# M710.net
KiCad netlist of a schematic drawn in EAGLE
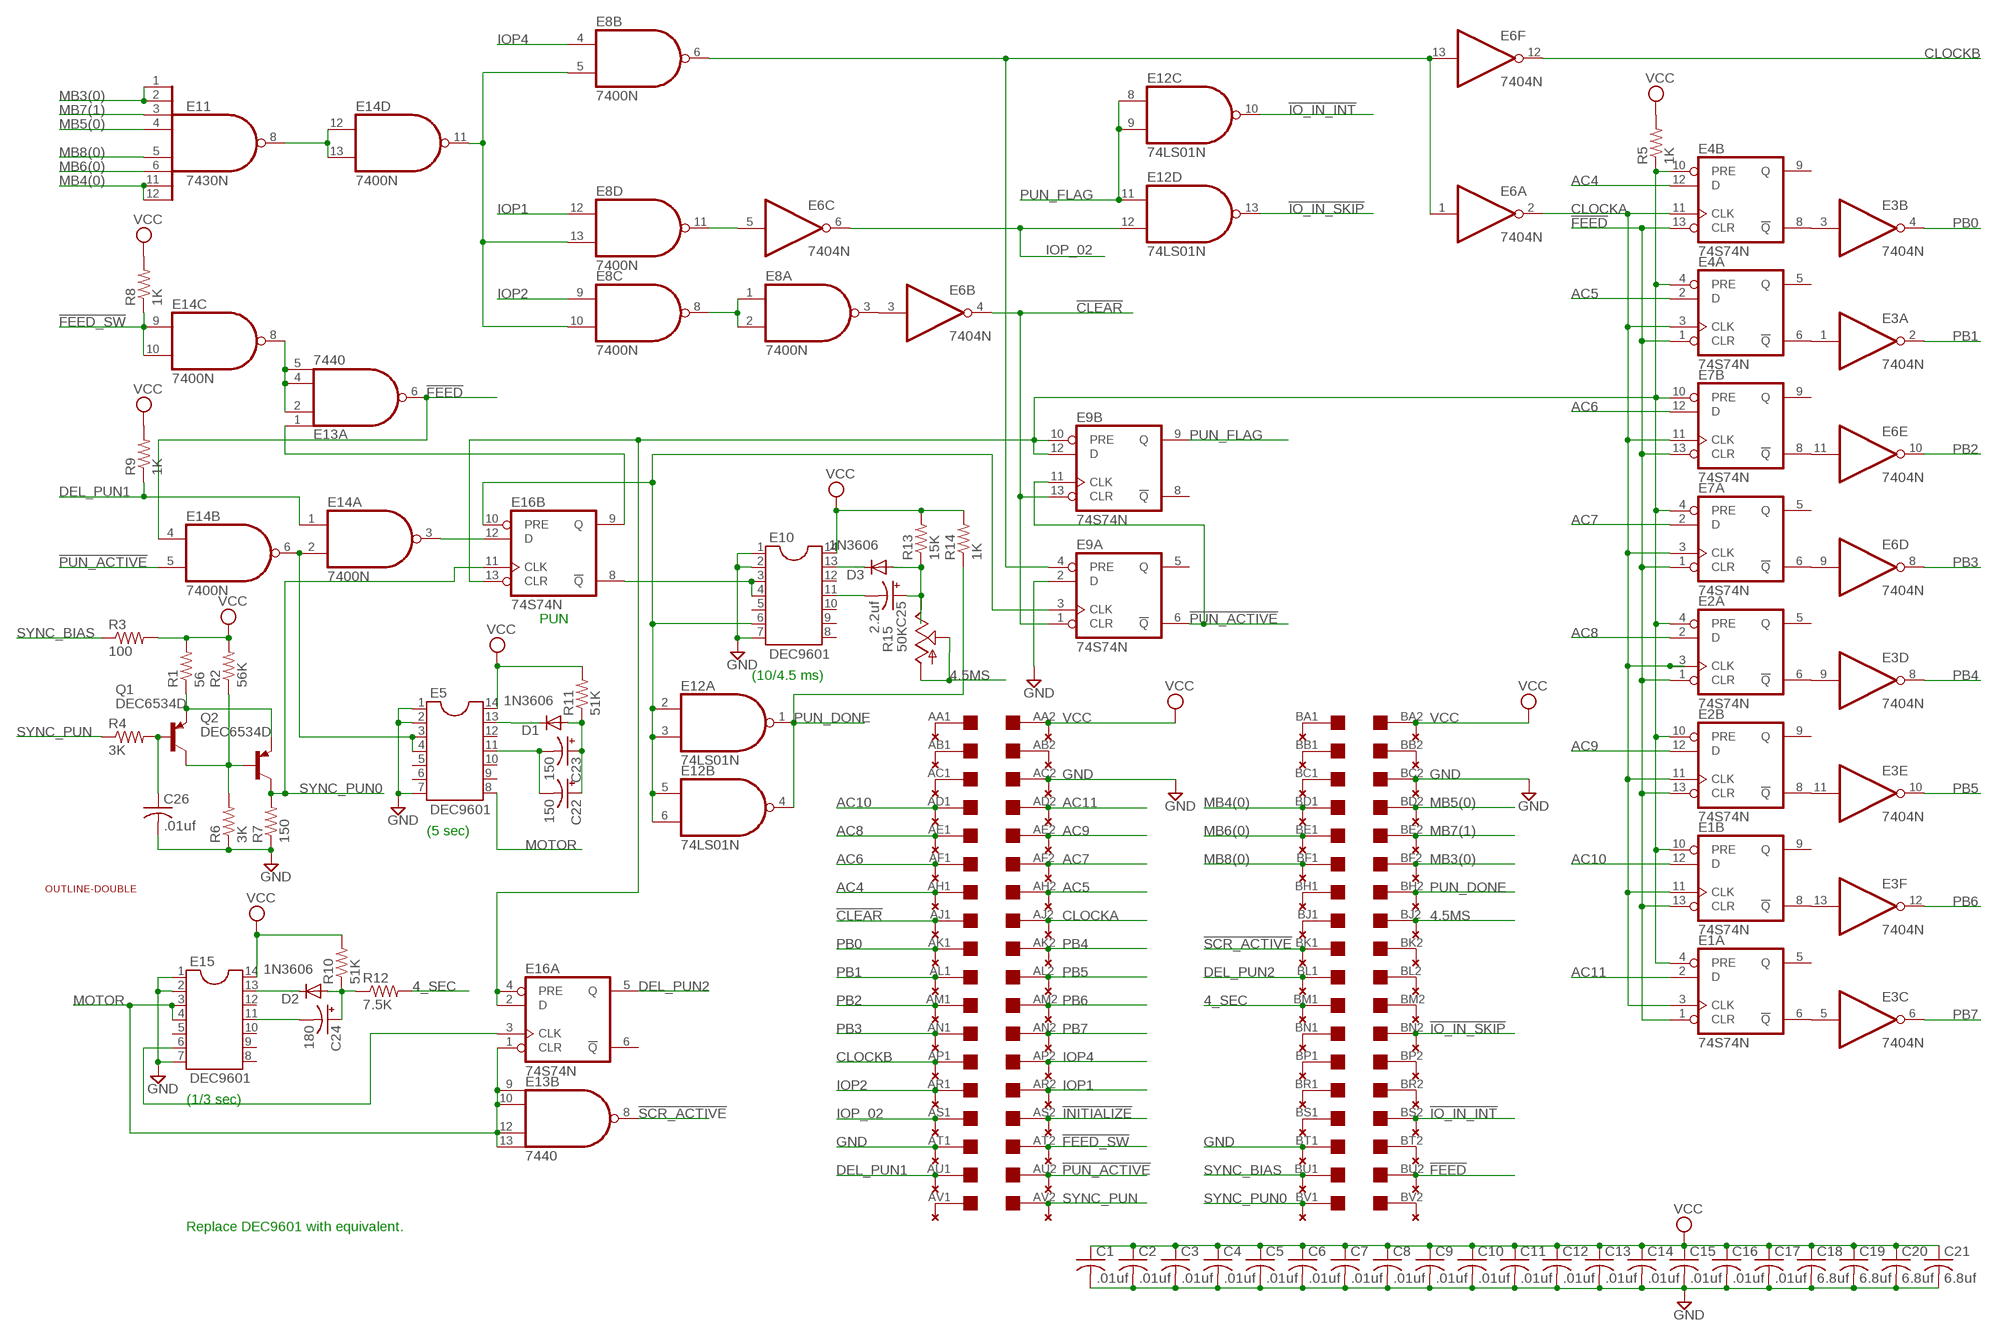
[diagram p0: schematic, sheet 1]

(export (version "E")
  (design (tool "Eeschema 10.0.6"))
  (components
    (comp (ref "C1")
      (value ".01uf")
      (footprint "eagle-import:C050-025X075")
      (libsource (lib "eagle-import") (part "C-US050-025X075"))
    )
    (comp (ref "C2")
      (value ".01uf")
      (footprint "eagle-import:C050-025X075")
      (libsource (lib "eagle-import") (part "C-US050-025X075"))
    )
    (comp (ref "C3")
      (value ".01uf")
      (footprint "eagle-import:C050-025X075")
      (libsource (lib "eagle-import") (part "C-US050-025X075"))
    )
    (comp (ref "C4")
      (value ".01uf")
      (footprint "eagle-import:C050-025X075")
      (libsource (lib "eagle-import") (part "C-US050-025X075"))
    )
    (comp (ref "C5")
      (value ".01uf")
      (footprint "eagle-import:C050-025X075")
      (libsource (lib "eagle-import") (part "C-US050-025X075"))
    )
    (comp (ref "C6")
      (value ".01uf")
      (footprint "eagle-import:C050-025X075")
      (libsource (lib "eagle-import") (part "C-US050-025X075"))
    )
    (comp (ref "C7")
      (value ".01uf")
      (footprint "eagle-import:C050-025X075")
      (libsource (lib "eagle-import") (part "C-US050-025X075"))
    )
    (comp (ref "C8")
      (value ".01uf")
      (footprint "eagle-import:C050-025X075")
      (libsource (lib "eagle-import") (part "C-US050-025X075"))
    )
    (comp (ref "C9")
      (value ".01uf")
      (footprint "eagle-import:C050-025X075")
      (libsource (lib "eagle-import") (part "C-US050-025X075"))
    )
    (comp (ref "C10")
      (value ".01uf")
      (footprint "eagle-import:C050-025X075")
      (libsource (lib "eagle-import") (part "C-US050-025X075"))
    )
    (comp (ref "C11")
      (value ".01uf")
      (footprint "eagle-import:C050-025X075")
      (libsource (lib "eagle-import") (part "C-US050-025X075"))
    )
    (comp (ref "C12")
      (value ".01uf")
      (footprint "eagle-import:C050-025X075")
      (libsource (lib "eagle-import") (part "C-US050-025X075"))
    )
    (comp (ref "C13")
      (value ".01uf")
      (footprint "eagle-import:C050-025X075")
      (libsource (lib "eagle-import") (part "C-US050-025X075"))
    )
    (comp (ref "C14")
      (value ".01uf")
      (footprint "eagle-import:C050-025X075")
      (libsource (lib "eagle-import") (part "C-US050-025X075"))
    )
    (comp (ref "C15")
      (value ".01uf")
      (footprint "eagle-import:C050-025X075")
      (libsource (lib "eagle-import") (part "C-US050-025X075"))
    )
    (comp (ref "C16")
      (value ".01uf")
      (footprint "eagle-import:C050-025X075")
      (libsource (lib "eagle-import") (part "C-US050-025X075"))
    )
    (comp (ref "C17")
      (value ".01uf")
      (footprint "eagle-import:C050-025X075")
      (libsource (lib "eagle-import") (part "C-US050-025X075"))
    )
    (comp (ref "C18")
      (value "6.8uf")
      (footprint "eagle-import:C150-054X183")
      (libsource (lib "eagle-import") (part "C-US150-054X183"))
    )
    (comp (ref "C19")
      (value "6.8uf")
      (footprint "eagle-import:C150-054X183")
      (libsource (lib "eagle-import") (part "C-US150-054X183"))
    )
    (comp (ref "C20")
      (value "6.8uf")
      (footprint "eagle-import:C150-054X183")
      (libsource (lib "eagle-import") (part "C-US150-054X183"))
    )
    (comp (ref "C21")
      (value "6.8uf")
      (footprint "eagle-import:C150-054X183")
      (libsource (lib "eagle-import") (part "C-US150-054X183"))
    )
    (comp (ref "C22")
      (value "150")
      (footprint "eagle-import:E5-8,5")
      (libsource (lib "eagle-import") (part "CPOL-USE5-8.5"))
    )
    (comp (ref "C23")
      (value "150")
      (footprint "eagle-import:E5-8,5")
      (libsource (lib "eagle-import") (part "CPOL-USE5-8.5"))
    )
    (comp (ref "C24")
      (value "180")
      (footprint "eagle-import:E5-8,5")
      (libsource (lib "eagle-import") (part "CPOL-USE5-8.5"))
    )
    (comp (ref "C25")
      (value "2.2uf")
      (footprint "eagle-import:E5-8,5")
      (libsource (lib "eagle-import") (part "CPOL-USE5-8.5"))
    )
    (comp (ref "C26")
      (value ".01uf")
      (footprint "eagle-import:C050-025X075")
      (libsource (lib "eagle-import") (part "C-US050-025X075"))
    )
    (comp (ref "D1")
      (value "1N3606")
      (footprint "eagle-import:DO41-10")
      (libsource (lib "eagle-import") (part "1N4004"))
    )
    (comp (ref "D2")
      (value "1N3606")
      (footprint "eagle-import:DO41-10")
      (libsource (lib "eagle-import") (part "1N4004"))
    )
    (comp (ref "D3")
      (value "1N3606")
      (footprint "eagle-import:DO41-10")
      (libsource (lib "eagle-import") (part "1N4004"))
    )
    (comp (ref "E1")
      (value "74S74N")
      (footprint "eagle-import:DIL14")
      (libsource (lib "eagle-import") (part "7474NS"))
    )
    (comp (ref "E2")
      (value "74S74N")
      (footprint "eagle-import:DIL14")
      (libsource (lib "eagle-import") (part "7474NS"))
    )
    (comp (ref "E3")
      (value "7404N")
      (footprint "eagle-import:DIL14")
      (libsource (lib "eagle-import") (part "7404N"))
    )
    (comp (ref "E4")
      (value "74S74N")
      (footprint "eagle-import:DIL14")
      (libsource (lib "eagle-import") (part "7474NS"))
    )
    (comp (ref "E5")
      (value "DEC9601")
      (footprint "eagle-import:DIL14")
      (libsource (lib "eagle-import") (part "DIL14"))
    )
    (comp (ref "E6")
      (value "7404N")
      (footprint "eagle-import:DIL14")
      (libsource (lib "eagle-import") (part "7404N"))
    )
    (comp (ref "E7")
      (value "74S74N")
      (footprint "eagle-import:DIL14")
      (libsource (lib "eagle-import") (part "7474NS"))
    )
    (comp (ref "E8")
      (value "7400N")
      (footprint "eagle-import:DIL14")
      (libsource (lib "eagle-import") (part "7400N"))
    )
    (comp (ref "E9")
      (value "74S74N")
      (footprint "eagle-import:DIL14")
      (libsource (lib "eagle-import") (part "7474NS"))
    )
    (comp (ref "E10")
      (value "DEC9601")
      (footprint "eagle-import:DIL14")
      (libsource (lib "eagle-import") (part "DIL14"))
    )
    (comp (ref "E11")
      (value "7430N")
      (footprint "eagle-import:DIL14")
      (libsource (lib "eagle-import") (part "7430N"))
    )
    (comp (ref "E12")
      (value "74LS01N")
      (footprint "eagle-import:DIL14")
      (libsource (lib "eagle-import") (part "7401NLS"))
    )
    (comp (ref "E13")
      (value "7440")
      (footprint "eagle-import:DIL14")
      (libsource (lib "eagle-import") (part "7420NS"))
    )
    (comp (ref "E14")
      (value "7400N")
      (footprint "eagle-import:DIL14")
      (libsource (lib "eagle-import") (part "7400N"))
    )
    (comp (ref "E15")
      (value "DEC9601")
      (footprint "eagle-import:DIL14")
      (libsource (lib "eagle-import") (part "DIL14"))
    )
    (comp (ref "E16")
      (value "74S74N")
      (footprint "eagle-import:DIL14")
      (libsource (lib "eagle-import") (part "7474NS"))
    )
    (comp (ref "Q1")
      (value "DEC6534D")
      (footprint "eagle-import:TO92")
      (libsource (lib "eagle-import") (part "2N3906"))
    )
    (comp (ref "Q2")
      (value "DEC6534D")
      (footprint "eagle-import:TO92")
      (libsource (lib "eagle-import") (part "2N3906"))
    )
    (comp (ref "R1")
      (value "56")
      (footprint "eagle-import:0207_7")
      (libsource (lib "eagle-import") (part "R-US_0207/7"))
    )
    (comp (ref "R2")
      (value "56K")
      (footprint "eagle-import:0207_7")
      (libsource (lib "eagle-import") (part "R-US_0207/7"))
    )
    (comp (ref "R3")
      (value "100")
      (footprint "eagle-import:0207_7")
      (libsource (lib "eagle-import") (part "R-US_0207/7"))
    )
    (comp (ref "R4")
      (value "3K")
      (footprint "eagle-import:0207_7")
      (libsource (lib "eagle-import") (part "R-US_0207/7"))
    )
    (comp (ref "R5")
      (value "1K")
      (footprint "eagle-import:0207_7")
      (libsource (lib "eagle-import") (part "R-US_0207/7"))
    )
    (comp (ref "R6")
      (value "3K")
      (footprint "eagle-import:0207_7")
      (libsource (lib "eagle-import") (part "R-US_0207/7"))
    )
    (comp (ref "R7")
      (value "150")
      (footprint "eagle-import:0207_7")
      (libsource (lib "eagle-import") (part "R-US_0207/7"))
    )
    (comp (ref "R8")
      (value "1K")
      (footprint "eagle-import:0207_7")
      (libsource (lib "eagle-import") (part "R-US_0207/7"))
    )
    (comp (ref "R9")
      (value "1K")
      (footprint "eagle-import:0207_7")
      (libsource (lib "eagle-import") (part "R-US_0207/7"))
    )
    (comp (ref "R10")
      (value "51K")
      (footprint "eagle-import:0207_7")
      (libsource (lib "eagle-import") (part "R-US_0207/7"))
    )
    (comp (ref "R11")
      (value "51K")
      (footprint "eagle-import:0207_7")
      (libsource (lib "eagle-import") (part "R-US_0207/7"))
    )
    (comp (ref "R12")
      (value "7.5K")
      (footprint "eagle-import:0207_7")
      (libsource (lib "eagle-import") (part "R-US_0207/7"))
    )
    (comp (ref "R13")
      (value "15K")
      (footprint "eagle-import:0207_7")
      (libsource (lib "eagle-import") (part "R-US_0207/7"))
    )
    (comp (ref "R14")
      (value "1K")
      (footprint "eagle-import:0207_7")
      (libsource (lib "eagle-import") (part "R-US_0207/7"))
    )
    (comp (ref "R15")
      (value "50K")
      (footprint "eagle-import:PT-SPIN")
      (libsource (lib "eagle-import") (part "TRIM_US-PTSPIN"))
    )
    (comp (ref "U$1")
      (value "OUTLINE-DOUBLE")
      (footprint "eagle-import:DOUBLE")
      (libsource (lib "eagle-import") (part "OUTLINE-DOUBLE"))
    )
    (comp (ref "U$2")
      (value "DOUBLE")
      (footprint "eagle-import:EDGE-CON4")
      (libsource (lib "eagle-import") (part "DOUBLE"))
    )
    (comp (ref "U$5")
      (value "THRU-HOLE2")
      (footprint "eagle-import:THRU-HOLEB")
      (libsource (lib "eagle-import") (part "THRU-HOLE2"))
    )
    (comp (ref "U$7")
      (value "THRU-HOLE2")
      (footprint "eagle-import:THRU-HOLEB")
      (libsource (lib "eagle-import") (part "THRU-HOLE2"))
    )
  )
  (nets
    (net (code "1") (name "/4.5MS") (class "Default")
      (node (ref "R15") (pin "A") (pinfunction "A_A") (pintype "passive"))
      (node (ref "R15") (pin "S") (pinfunction "S_S") (pintype "passive"))
      (node (ref "U$2") (pin "BJ2") (pinfunction "1_BJ2") (pintype "bidirectional"))
      (node (ref "U$5") (pin "J2") (pinfunction "P$1_J2") (pintype "passive"))
    )
    (net (code "2") (name "/4_SEC") (class "Default")
      (node (ref "R12") (pin "2") (pinfunction "2_2") (pintype "passive"))
      (node (ref "U$2") (pin "BM1") (pinfunction "1_BM1") (pintype "bidirectional"))
      (node (ref "U$5") (pin "M1") (pinfunction "P$1_M1") (pintype "passive"))
    )
    (net (code "3") (name "/AC4") (class "Default")
      (node (ref "E4") (pin "12") (pinfunction "D_12") (pintype "input"))
      (node (ref "U$2") (pin "AH1") (pinfunction "1_AH1") (pintype "bidirectional"))
      (node (ref "U$7") (pin "H1") (pinfunction "P$1_H1") (pintype "passive"))
    )
    (net (code "4") (name "/AC5") (class "Default")
      (node (ref "E4") (pin "2") (pinfunction "D_2") (pintype "input"))
      (node (ref "U$2") (pin "AH2") (pinfunction "1_AH2") (pintype "bidirectional"))
      (node (ref "U$7") (pin "H2") (pinfunction "P$1_H2") (pintype "passive"))
    )
    (net (code "5") (name "/AC6") (class "Default")
      (node (ref "E7") (pin "12") (pinfunction "D_12") (pintype "input"))
      (node (ref "U$2") (pin "AF1") (pinfunction "1_AF1") (pintype "bidirectional"))
      (node (ref "U$7") (pin "F1") (pinfunction "P$1_F1") (pintype "passive"))
    )
    (net (code "6") (name "/AC7") (class "Default")
      (node (ref "E7") (pin "2") (pinfunction "D_2") (pintype "input"))
      (node (ref "U$2") (pin "AF2") (pinfunction "1_AF2") (pintype "bidirectional"))
      (node (ref "U$7") (pin "F2") (pinfunction "P$1_F2") (pintype "passive"))
    )
    (net (code "7") (name "/AC8") (class "Default")
      (node (ref "E2") (pin "2") (pinfunction "D_2") (pintype "input"))
      (node (ref "U$2") (pin "AE1") (pinfunction "1_AE1") (pintype "bidirectional"))
      (node (ref "U$7") (pin "E1") (pinfunction "P$1_E1") (pintype "passive"))
    )
    (net (code "8") (name "/AC9") (class "Default")
      (node (ref "E2") (pin "12") (pinfunction "D_12") (pintype "input"))
      (node (ref "U$2") (pin "AE2") (pinfunction "1_AE2") (pintype "bidirectional"))
      (node (ref "U$7") (pin "E2") (pinfunction "P$1_E2") (pintype "passive"))
    )
    (net (code "9") (name "/AC10") (class "Default")
      (node (ref "E1") (pin "12") (pinfunction "D_12") (pintype "input"))
      (node (ref "U$2") (pin "AD1") (pinfunction "1_AD1") (pintype "bidirectional"))
      (node (ref "U$7") (pin "D1") (pinfunction "P$1_D1") (pintype "passive"))
    )
    (net (code "10") (name "/AC11") (class "Default")
      (node (ref "E1") (pin "2") (pinfunction "D_2") (pintype "input"))
      (node (ref "U$2") (pin "AD2") (pinfunction "1_AD2") (pintype "bidirectional"))
      (node (ref "U$7") (pin "D2") (pinfunction "P$1_D2") (pintype "passive"))
    )
    (net (code "11") (name "/CLOCKA") (class "Default")
      (node (ref "E1") (pin "11") (pinfunction "CLK_11") (pintype "input"))
      (node (ref "E1") (pin "3") (pinfunction "CLK_3") (pintype "input"))
      (node (ref "E2") (pin "11") (pinfunction "CLK_11") (pintype "input"))
      (node (ref "E2") (pin "3") (pinfunction "CLK_3") (pintype "input"))
      (node (ref "E4") (pin "11") (pinfunction "CLK_11") (pintype "input"))
      (node (ref "E4") (pin "3") (pinfunction "CLK_3") (pintype "input"))
      (node (ref "E6") (pin "2") (pinfunction "O_2") (pintype "output"))
      (node (ref "E7") (pin "11") (pinfunction "CLK_11") (pintype "input"))
      (node (ref "E7") (pin "3") (pinfunction "CLK_3") (pintype "input"))
      (node (ref "U$2") (pin "AJ2") (pinfunction "1_AJ2") (pintype "bidirectional"))
      (node (ref "U$7") (pin "J2") (pinfunction "P$1_J2") (pintype "passive"))
    )
    (net (code "12") (name "/CLOCKB") (class "Default")
      (node (ref "E6") (pin "12") (pinfunction "O_12") (pintype "output"))
      (node (ref "U$2") (pin "AP1") (pinfunction "1_AP1") (pintype "bidirectional"))
      (node (ref "U$7") (pin "P1") (pinfunction "P$1_P1") (pintype "passive"))
    )
    (net (code "13") (name "/DEL_PUN1") (class "Default")
      (node (ref "E14") (pin "1") (pinfunction "I0_1") (pintype "input"))
      (node (ref "R9") (pin "1") (pinfunction "1_1") (pintype "passive"))
      (node (ref "U$2") (pin "AU1") (pinfunction "1_AU1") (pintype "bidirectional"))
      (node (ref "U$7") (pin "U1") (pinfunction "P$1_U1") (pintype "passive"))
    )
    (net (code "14") (name "/DEL_PUN2") (class "Default")
      (node (ref "E16") (pin "5") (pinfunction "Q_5") (pintype "output"))
      (node (ref "U$2") (pin "BL1") (pinfunction "1_BL1") (pintype "bidirectional"))
      (node (ref "U$5") (pin "L1") (pinfunction "P$1_L1") (pintype "passive"))
    )
    (net (code "15") (name "/IOP1") (class "Default")
      (node (ref "E8") (pin "12") (pinfunction "I0_12") (pintype "input"))
      (node (ref "U$2") (pin "AR2") (pinfunction "1_AR2") (pintype "bidirectional"))
      (node (ref "U$7") (pin "R2") (pinfunction "P$1_R2") (pintype "passive"))
    )
    (net (code "16") (name "/IOP2") (class "Default")
      (node (ref "E8") (pin "9") (pinfunction "I0_9") (pintype "input"))
      (node (ref "U$2") (pin "AR1") (pinfunction "1_AR1") (pintype "bidirectional"))
      (node (ref "U$7") (pin "R1") (pinfunction "P$1_R1") (pintype "passive"))
    )
    (net (code "17") (name "/IOP4") (class "Default")
      (node (ref "E8") (pin "4") (pinfunction "I0_4") (pintype "input"))
      (node (ref "U$2") (pin "AP2") (pinfunction "1_AP2") (pintype "bidirectional"))
      (node (ref "U$7") (pin "P2") (pinfunction "P$1_P2") (pintype "passive"))
    )
    (net (code "18") (name "/IOP_02") (class "Default")
      (node (ref "E12") (pin "12") (pinfunction "I1_12") (pintype "input"))
      (node (ref "E6") (pin "6") (pinfunction "O_6") (pintype "output"))
      (node (ref "U$2") (pin "AS1") (pinfunction "1_AS1") (pintype "bidirectional"))
      (node (ref "U$7") (pin "S1") (pinfunction "P$1_S1") (pintype "passive"))
    )
    (net (code "19") (name "/MB3(0)") (class "Default")
      (node (ref "E11") (pin "1") (pinfunction "I0_1") (pintype "input"))
      (node (ref "E11") (pin "2") (pinfunction "I1_2") (pintype "input"))
      (node (ref "U$2") (pin "BF2") (pinfunction "1_BF2") (pintype "bidirectional"))
      (node (ref "U$5") (pin "F2") (pinfunction "P$1_F2") (pintype "passive"))
    )
    (net (code "20") (name "/MB4(0)") (class "Default")
      (node (ref "E11") (pin "11") (pinfunction "I6_11") (pintype "input"))
      (node (ref "E11") (pin "12") (pinfunction "I7_12") (pintype "input"))
      (node (ref "U$2") (pin "BD1") (pinfunction "1_BD1") (pintype "bidirectional"))
      (node (ref "U$5") (pin "D1") (pinfunction "P$1_D1") (pintype "passive"))
    )
    (net (code "21") (name "/MB5(0)") (class "Default")
      (node (ref "E11") (pin "4") (pinfunction "I3_4") (pintype "input"))
      (node (ref "U$2") (pin "BD2") (pinfunction "1_BD2") (pintype "bidirectional"))
      (node (ref "U$5") (pin "D2") (pinfunction "P$1_D2") (pintype "passive"))
    )
    (net (code "22") (name "/MB6(0)") (class "Default")
      (node (ref "E11") (pin "6") (pinfunction "I5_6") (pintype "input"))
      (node (ref "U$2") (pin "BE1") (pinfunction "1_BE1") (pintype "bidirectional"))
      (node (ref "U$5") (pin "E1") (pinfunction "P$1_E1") (pintype "passive"))
    )
    (net (code "23") (name "/MB7(1)") (class "Default")
      (node (ref "E11") (pin "3") (pinfunction "I2_3") (pintype "input"))
      (node (ref "U$2") (pin "BE2") (pinfunction "1_BE2") (pintype "bidirectional"))
      (node (ref "U$5") (pin "E2") (pinfunction "P$1_E2") (pintype "passive"))
    )
    (net (code "24") (name "/MB8(0)") (class "Default")
      (node (ref "E11") (pin "5") (pinfunction "I4_5") (pintype "input"))
      (node (ref "U$2") (pin "BF1") (pinfunction "1_BF1") (pintype "bidirectional"))
      (node (ref "U$5") (pin "F1") (pinfunction "P$1_F1") (pintype "passive"))
    )
    (net (code "25") (name "/MOTOR") (class "Default")
      (node (ref "E13") (pin "10") (pinfunction "I1_10") (pintype "input"))
      (node (ref "E13") (pin "12") (pinfunction "I2_12") (pintype "input"))
      (node (ref "E13") (pin "13") (pinfunction "I3_13") (pintype "input"))
      (node (ref "E13") (pin "9") (pinfunction "I0_9") (pintype "input"))
      (node (ref "E15") (pin "3") (pinfunction "3_3") (pintype "passive"))
      (node (ref "E15") (pin "4") (pinfunction "4_4") (pintype "passive"))
      (node (ref "E16") (pin "1") (pinfunction "CLR_1") (pintype "input"))
      (node (ref "E5") (pin "8") (pinfunction "8_8") (pintype "passive"))
    )
    (net (code "26") (name "/PB0") (class "Default")
      (node (ref "E3") (pin "4") (pinfunction "O_4") (pintype "output"))
      (node (ref "U$2") (pin "AK1") (pinfunction "1_AK1") (pintype "bidirectional"))
      (node (ref "U$7") (pin "K1") (pinfunction "P$1_K1") (pintype "passive"))
    )
    (net (code "27") (name "/PB1") (class "Default")
      (node (ref "E3") (pin "2") (pinfunction "O_2") (pintype "output"))
      (node (ref "U$2") (pin "AL1") (pinfunction "1_AL1") (pintype "bidirectional"))
      (node (ref "U$7") (pin "L1") (pinfunction "P$1_L1") (pintype "passive"))
    )
    (net (code "28") (name "/PB2") (class "Default")
      (node (ref "E6") (pin "10") (pinfunction "O_10") (pintype "output"))
      (node (ref "U$2") (pin "AM1") (pinfunction "1_AM1") (pintype "bidirectional"))
      (node (ref "U$7") (pin "M1") (pinfunction "P$1_M1") (pintype "passive"))
    )
    (net (code "29") (name "/PB3") (class "Default")
      (node (ref "E6") (pin "8") (pinfunction "O_8") (pintype "output"))
      (node (ref "U$2") (pin "AN1") (pinfunction "1_AN1") (pintype "bidirectional"))
      (node (ref "U$7") (pin "N1") (pinfunction "P$1_N1") (pintype "passive"))
    )
    (net (code "30") (name "/PB4") (class "Default")
      (node (ref "E3") (pin "8") (pinfunction "O_8") (pintype "output"))
      (node (ref "U$2") (pin "AK2") (pinfunction "1_AK2") (pintype "bidirectional"))
      (node (ref "U$7") (pin "K2") (pinfunction "P$1_K2") (pintype "passive"))
    )
    (net (code "31") (name "/PB5") (class "Default")
      (node (ref "E3") (pin "10") (pinfunction "O_10") (pintype "output"))
      (node (ref "U$2") (pin "AL2") (pinfunction "1_AL2") (pintype "bidirectional"))
      (node (ref "U$7") (pin "L2") (pinfunction "P$1_L2") (pintype "passive"))
    )
    (net (code "32") (name "/PB6") (class "Default")
      (node (ref "E3") (pin "12") (pinfunction "O_12") (pintype "output"))
      (node (ref "U$2") (pin "AM2") (pinfunction "1_AM2") (pintype "bidirectional"))
      (node (ref "U$7") (pin "M2") (pinfunction "P$1_M2") (pintype "passive"))
    )
    (net (code "33") (name "/PB7") (class "Default")
      (node (ref "E3") (pin "6") (pinfunction "O_6") (pintype "output"))
      (node (ref "U$2") (pin "AN2") (pinfunction "1_AN2") (pintype "bidirectional"))
      (node (ref "U$7") (pin "N2") (pinfunction "P$1_N2") (pintype "passive"))
    )
    (net (code "34") (name "/PUN_DONE") (class "Default")
      (node (ref "E12") (pin "1") (pinfunction "O_1") (pintype "open_collector"))
      (node (ref "E12") (pin "4") (pinfunction "O_4") (pintype "open_collector"))
      (node (ref "R14") (pin "1") (pinfunction "1_1") (pintype "passive"))
      (node (ref "U$2") (pin "BH2") (pinfunction "1_BH2") (pintype "bidirectional"))
      (node (ref "U$5") (pin "H2") (pinfunction "P$1_H2") (pintype "passive"))
    )
    (net (code "35") (name "/PUN_FLAG") (class "Default")
      (node (ref "E12") (pin "11") (pinfunction "I0_11") (pintype "input"))
      (node (ref "E12") (pin "8") (pinfunction "I0_8") (pintype "input"))
      (node (ref "E12") (pin "9") (pinfunction "I1_9") (pintype "input"))
      (node (ref "E9") (pin "9") (pinfunction "Q_9") (pintype "output"))
    )
    (net (code "36") (name "/SYNC_BIAS") (class "Default")
      (node (ref "R3") (pin "1") (pinfunction "1_1") (pintype "passive"))
      (node (ref "U$2") (pin "BU1") (pinfunction "1_BU1") (pintype "bidirectional"))
      (node (ref "U$5") (pin "U1") (pinfunction "P$1_U1") (pintype "passive"))
    )
    (net (code "37") (name "/SYNC_PUN") (class "Default")
      (node (ref "R4") (pin "1") (pinfunction "1_1") (pintype "passive"))
      (node (ref "U$2") (pin "AV2") (pinfunction "1_AV2") (pintype "bidirectional"))
      (node (ref "U$7") (pin "V2") (pinfunction "P$1_V2") (pintype "passive"))
    )
    (net (code "38") (name "/SYNC_PUN0") (class "Default")
      (node (ref "E16") (pin "11") (pinfunction "CLK_11") (pintype "input"))
      (node (ref "Q2") (pin "1") (pinfunction "C_1") (pintype "passive"))
      (node (ref "R7") (pin "2") (pinfunction "2_2") (pintype "passive"))
      (node (ref "U$2") (pin "BV1") (pinfunction "1_BV1") (pintype "bidirectional"))
      (node (ref "U$5") (pin "V1") (pinfunction "P$1_V1") (pintype "passive"))
    )
    (net (code "39") (name "/~{CLEAR}") (class "Default")
      (node (ref "E6") (pin "4") (pinfunction "O_4") (pintype "output"))
      (node (ref "E9") (pin "1") (pinfunction "CLR_1") (pintype "input"))
      (node (ref "E9") (pin "13") (pinfunction "CLR_13") (pintype "input"))
      (node (ref "U$2") (pin "AJ1") (pinfunction "1_AJ1") (pintype "bidirectional"))
      (node (ref "U$7") (pin "J1") (pinfunction "P$1_J1") (pintype "passive"))
    )
    (net (code "40") (name "/~{FEED_SW}") (class "Default")
      (node (ref "E14") (pin "10") (pinfunction "I1_10") (pintype "input"))
      (node (ref "E14") (pin "9") (pinfunction "I0_9") (pintype "input"))
      (node (ref "R8") (pin "1") (pinfunction "1_1") (pintype "passive"))
      (node (ref "U$2") (pin "AT2") (pinfunction "1_AT2") (pintype "bidirectional"))
      (node (ref "U$7") (pin "T2") (pinfunction "P$1_T2") (pintype "passive"))
    )
    (net (code "41") (name "/~{FEED}") (class "Default")
      (node (ref "E1") (pin "1") (pinfunction "CLR_1") (pintype "input"))
      (node (ref "E1") (pin "13") (pinfunction "CLR_13") (pintype "input"))
      (node (ref "E13") (pin "6") (pinfunction "O_6") (pintype "output"))
      (node (ref "E14") (pin "4") (pinfunction "I0_4") (pintype "input"))
      (node (ref "E2") (pin "1") (pinfunction "CLR_1") (pintype "input"))
      (node (ref "E2") (pin "13") (pinfunction "CLR_13") (pintype "input"))
      (node (ref "E4") (pin "1") (pinfunction "CLR_1") (pintype "input"))
      (node (ref "E4") (pin "13") (pinfunction "CLR_13") (pintype "input"))
      (node (ref "E7") (pin "1") (pinfunction "CLR_1") (pintype "input"))
      (node (ref "E7") (pin "13") (pinfunction "CLR_13") (pintype "input"))
      (node (ref "U$2") (pin "BU2") (pinfunction "1_BU2") (pintype "bidirectional"))
      (node (ref "U$5") (pin "U2") (pinfunction "P$1_U2") (pintype "passive"))
    )
    (net (code "42") (name "/~{INITIALIZE}") (class "Default")
      (node (ref "U$2") (pin "AS2") (pinfunction "1_AS2") (pintype "bidirectional"))
      (node (ref "U$7") (pin "S2") (pinfunction "P$1_S2") (pintype "passive"))
    )
    (net (code "43") (name "/~{IO_IN_INT}") (class "Default")
      (node (ref "E12") (pin "10") (pinfunction "O_10") (pintype "open_collector"))
      (node (ref "U$2") (pin "BS2") (pinfunction "1_BS2") (pintype "bidirectional"))
      (node (ref "U$5") (pin "S2") (pinfunction "P$1_S2") (pintype "passive"))
    )
    (net (code "44") (name "/~{IO_IN_SKIP}") (class "Default")
      (node (ref "E12") (pin "13") (pinfunction "O_13") (pintype "open_collector"))
      (node (ref "U$2") (pin "BN2") (pinfunction "1_BN2") (pintype "bidirectional"))
      (node (ref "U$5") (pin "N2") (pinfunction "P$1_N2") (pintype "passive"))
    )
    (net (code "45") (name "/~{PUN_ACTIVE}") (class "Default")
      (node (ref "E14") (pin "5") (pinfunction "I1_5") (pintype "input"))
      (node (ref "E9") (pin "11") (pinfunction "CLK_11") (pintype "input"))
      (node (ref "E9") (pin "6") (pinfunction "~{Q}_6") (pintype "output"))
      (node (ref "U$2") (pin "AU2") (pinfunction "1_AU2") (pintype "bidirectional"))
      (node (ref "U$7") (pin "U2") (pinfunction "P$1_U2") (pintype "passive"))
    )
    (net (code "46") (name "/~{SCR_ACTIVE}") (class "Default")
      (node (ref "E13") (pin "8") (pinfunction "O_8") (pintype "output"))
      (node (ref "U$2") (pin "BK1") (pinfunction "1_BK1") (pintype "bidirectional"))
      (node (ref "U$5") (pin "K1") (pinfunction "P$1_K1") (pintype "passive"))
    )
    (net (code "47") (name "GND") (class "Default")
      (node (ref "C1") (pin "2") (pinfunction "2_2") (pintype "passive"))
      (node (ref "C10") (pin "2") (pinfunction "2_2") (pintype "passive"))
      (node (ref "C11") (pin "2") (pinfunction "2_2") (pintype "passive"))
      (node (ref "C12") (pin "2") (pinfunction "2_2") (pintype "passive"))
      (node (ref "C13") (pin "2") (pinfunction "2_2") (pintype "passive"))
      (node (ref "C14") (pin "2") (pinfunction "2_2") (pintype "passive"))
      (node (ref "C15") (pin "2") (pinfunction "2_2") (pintype "passive"))
      (node (ref "C16") (pin "2") (pinfunction "2_2") (pintype "passive"))
      (node (ref "C17") (pin "2") (pinfunction "2_2") (pintype "passive"))
      (node (ref "C18") (pin "2") (pinfunction "2_2") (pintype "passive"))
      (node (ref "C19") (pin "2") (pinfunction "2_2") (pintype "passive"))
      (node (ref "C2") (pin "2") (pinfunction "2_2") (pintype "passive"))
      (node (ref "C20") (pin "2") (pinfunction "2_2") (pintype "passive"))
      (node (ref "C21") (pin "2") (pinfunction "2_2") (pintype "passive"))
      (node (ref "C26") (pin "2") (pinfunction "2_2") (pintype "passive"))
      (node (ref "C3") (pin "2") (pinfunction "2_2") (pintype "passive"))
      (node (ref "C4") (pin "2") (pinfunction "2_2") (pintype "passive"))
      (node (ref "C5") (pin "2") (pinfunction "2_2") (pintype "passive"))
      (node (ref "C6") (pin "2") (pinfunction "2_2") (pintype "passive"))
      (node (ref "C7") (pin "2") (pinfunction "2_2") (pintype "passive"))
      (node (ref "C8") (pin "2") (pinfunction "2_2") (pintype "passive"))
      (node (ref "C9") (pin "2") (pinfunction "2_2") (pintype "passive"))
      (node (ref "E10") (pin "1") (pinfunction "1_1") (pintype "passive"))
      (node (ref "E10") (pin "2") (pinfunction "2_2") (pintype "passive"))
      (node (ref "E10") (pin "7") (pinfunction "7_7") (pintype "passive"))
      (node (ref "E15") (pin "1") (pinfunction "1_1") (pintype "passive"))
      (node (ref "E15") (pin "2") (pinfunction "2_2") (pintype "passive"))
      (node (ref "E15") (pin "7") (pinfunction "7_7") (pintype "passive"))
      (node (ref "E5") (pin "1") (pinfunction "1_1") (pintype "passive"))
      (node (ref "E5") (pin "2") (pinfunction "2_2") (pintype "passive"))
      (node (ref "E5") (pin "7") (pinfunction "7_7") (pintype "passive"))
      (node (ref "E9") (pin "2") (pinfunction "D_2") (pintype "input"))
      (node (ref "R6") (pin "1") (pinfunction "1_1") (pintype "passive"))
      (node (ref "R7") (pin "1") (pinfunction "1_1") (pintype "passive"))
      (node (ref "U$2") (pin "AC2") (pinfunction "1_AC2") (pintype "bidirectional"))
      (node (ref "U$2") (pin "AT1") (pinfunction "1_AT1") (pintype "bidirectional"))
      (node (ref "U$2") (pin "BC2") (pinfunction "1_BC2") (pintype "bidirectional"))
      (node (ref "U$2") (pin "BT1") (pinfunction "1_BT1") (pintype "bidirectional"))
      (node (ref "U$5") (pin "C2") (pinfunction "P$1_C2") (pintype "passive"))
      (node (ref "U$5") (pin "T1") (pinfunction "P$1_T1") (pintype "passive"))
      (node (ref "U$7") (pin "C2") (pinfunction "P$1_C2") (pintype "passive"))
      (node (ref "U$7") (pin "T1") (pinfunction "P$1_T1") (pintype "passive"))
    )
    (net (code "48") (name "Net-(C22-Pad+)") (class "Default")
      (node (ref "C22") (pin "+") (pinfunction "+_+") (pintype "passive"))
      (node (ref "C23") (pin "+") (pinfunction "+_+") (pintype "passive"))
      (node (ref "D1") (pin "A") (pinfunction "A_A") (pintype "passive"))
      (node (ref "R11") (pin "1") (pinfunction "1_1") (pintype "passive"))
    )
    (net (code "49") (name "Net-(C22-Pad-)") (class "Default")
      (node (ref "C22") (pin "-") (pinfunction "-_-") (pintype "passive"))
      (node (ref "C23") (pin "-") (pinfunction "-_-") (pintype "passive"))
      (node (ref "E5") (pin "11") (pinfunction "11_11") (pintype "passive"))
    )
    (net (code "50") (name "Net-(C24-Pad+)") (class "Default")
      (node (ref "C24") (pin "+") (pinfunction "+_+") (pintype "passive"))
      (node (ref "D2") (pin "A") (pinfunction "A_A") (pintype "passive"))
      (node (ref "R10") (pin "1") (pinfunction "1_1") (pintype "passive"))
      (node (ref "R12") (pin "1") (pinfunction "1_1") (pintype "passive"))
    )
    (net (code "51") (name "Net-(C24-Pad-)") (class "Default")
      (node (ref "C24") (pin "-") (pinfunction "-_-") (pintype "passive"))
      (node (ref "E15") (pin "11") (pinfunction "11_11") (pintype "passive"))
    )
    (net (code "52") (name "Net-(C25-Pad+)") (class "Default")
      (node (ref "C25") (pin "+") (pinfunction "+_+") (pintype "passive"))
      (node (ref "D3") (pin "A") (pinfunction "A_A") (pintype "passive"))
      (node (ref "R13") (pin "1") (pinfunction "1_1") (pintype "passive"))
      (node (ref "R15") (pin "E") (pinfunction "E_E") (pintype "passive"))
    )
    (net (code "53") (name "Net-(C25-Pad-)") (class "Default")
      (node (ref "C25") (pin "-") (pinfunction "-_-") (pintype "passive"))
      (node (ref "E10") (pin "11") (pinfunction "11_11") (pintype "passive"))
    )
    (net (code "54") (name "Net-(D1-PadC)") (class "Default")
      (node (ref "D1") (pin "C") (pinfunction "C_C") (pintype "passive"))
      (node (ref "E5") (pin "13") (pinfunction "13_13") (pintype "passive"))
    )
    (net (code "55") (name "Net-(D2-PadC)") (class "Default")
      (node (ref "D2") (pin "C") (pinfunction "C_C") (pintype "passive"))
      (node (ref "E15") (pin "13") (pinfunction "13_13") (pintype "passive"))
    )
    (net (code "56") (name "Net-(D3-PadC)") (class "Default")
      (node (ref "D3") (pin "C") (pinfunction "C_C") (pintype "passive"))
      (node (ref "E10") (pin "13") (pinfunction "13_13") (pintype "passive"))
    )
    (net (code "57") (name "Net-(E1A-~{Q})") (class "Default")
      (node (ref "E1") (pin "6") (pinfunction "~{Q}_6") (pintype "output"))
      (node (ref "E3") (pin "5") (pinfunction "I_5") (pintype "input"))
    )
    (net (code "58") (name "Net-(E1B-~{Q})") (class "Default")
      (node (ref "E1") (pin "8") (pinfunction "~{Q}_8") (pintype "output"))
      (node (ref "E3") (pin "13") (pinfunction "I_13") (pintype "input"))
    )
    (net (code "59") (name "Net-(E2A-~{Q})") (class "Default")
      (node (ref "E2") (pin "6") (pinfunction "~{Q}_6") (pintype "output"))
      (node (ref "E3") (pin "9") (pinfunction "I_9") (pintype "input"))
    )
    (net (code "60") (name "Net-(E2B-~{Q})") (class "Default")
      (node (ref "E2") (pin "8") (pinfunction "~{Q}_8") (pintype "output"))
      (node (ref "E3") (pin "11") (pinfunction "I_11") (pintype "input"))
    )
    (net (code "61") (name "Net-(E3A-I)") (class "Default")
      (node (ref "E3") (pin "1") (pinfunction "I_1") (pintype "input"))
      (node (ref "E4") (pin "6") (pinfunction "~{Q}_6") (pintype "output"))
    )
    (net (code "62") (name "Net-(E3B-I)") (class "Default")
      (node (ref "E3") (pin "3") (pinfunction "I_3") (pintype "input"))
      (node (ref "E4") (pin "8") (pinfunction "~{Q}_8") (pintype "output"))
    )
    (net (code "63") (name "Net-(E6A-I)") (class "Default")
      (node (ref "E6") (pin "1") (pinfunction "I_1") (pintype "input"))
      (node (ref "E6") (pin "13") (pinfunction "I_13") (pintype "input"))
      (node (ref "E8") (pin "6") (pinfunction "O_6") (pintype "output"))
      (node (ref "E9") (pin "4") (pinfunction "PRE_4") (pintype "input"))
    )
    (net (code "64") (name "Net-(E6B-I)") (class "Default")
      (node (ref "E6") (pin "3") (pinfunction "I_3") (pintype "input"))
      (node (ref "E8") (pin "3") (pinfunction "O_3") (pintype "output"))
    )
    (net (code "65") (name "Net-(E6C-I)") (class "Default")
      (node (ref "E6") (pin "5") (pinfunction "I_5") (pintype "input"))
      (node (ref "E8") (pin "11") (pinfunction "O_11") (pintype "output"))
    )
    (net (code "66") (name "Net-(E6D-I)") (class "Default")
      (node (ref "E6") (pin "9") (pinfunction "I_9") (pintype "input"))
      (node (ref "E7") (pin "6") (pinfunction "~{Q}_6") (pintype "output"))
    )
    (net (code "67") (name "Net-(E6E-I)") (class "Default")
      (node (ref "E6") (pin "11") (pinfunction "I_11") (pintype "input"))
      (node (ref "E7") (pin "8") (pinfunction "~{Q}_8") (pintype "output"))
    )
    (net (code "68") (name "Net-(E8A-I0)") (class "Default")
      (node (ref "E8") (pin "1") (pinfunction "I0_1") (pintype "input"))
      (node (ref "E8") (pin "2") (pinfunction "I1_2") (pintype "input"))
      (node (ref "E8") (pin "8") (pinfunction "O_8") (pintype "output"))
    )
    (net (code "69") (name "Net-(E11A-O)") (class "Default")
      (node (ref "E11") (pin "8") (pinfunction "O_8") (pintype "output"))
      (node (ref "E14") (pin "12") (pinfunction "I0_12") (pintype "input"))
      (node (ref "E14") (pin "13") (pinfunction "I1_13") (pintype "input"))
    )
    (net (code "70") (name "Net-(E12A-I0)") (class "Default")
      (node (ref "E10") (pin "6") (pinfunction "6_6") (pintype "passive"))
      (node (ref "E12") (pin "2") (pinfunction "I0_2") (pintype "input"))
      (node (ref "E12") (pin "3") (pinfunction "I1_3") (pintype "input"))
      (node (ref "E12") (pin "5") (pinfunction "I0_5") (pintype "input"))
      (node (ref "E12") (pin "6") (pinfunction "I1_6") (pintype "input"))
      (node (ref "E16") (pin "10") (pinfunction "PRE_10") (pintype "input"))
      (node (ref "E9") (pin "3") (pinfunction "CLK_3") (pintype "input"))
    )
    (net (code "71") (name "Net-(E13A-I0)") (class "Default")
      (node (ref "E13") (pin "1") (pinfunction "I0_1") (pintype "input"))
      (node (ref "E16") (pin "9") (pinfunction "Q_9") (pintype "output"))
    )
    (net (code "72") (name "Net-(E13A-I1)") (class "Default")
      (node (ref "E13") (pin "2") (pinfunction "I1_2") (pintype "input"))
      (node (ref "E13") (pin "4") (pinfunction "I2_4") (pintype "input"))
      (node (ref "E13") (pin "5") (pinfunction "I3_5") (pintype "input"))
      (node (ref "E14") (pin "8") (pinfunction "O_8") (pintype "output"))
    )
    (net (code "73") (name "Net-(E14A-I1)") (class "Default")
      (node (ref "E14") (pin "2") (pinfunction "I1_2") (pintype "input"))
      (node (ref "E14") (pin "6") (pinfunction "O_6") (pintype "output"))
      (node (ref "E5") (pin "3") (pinfunction "3_3") (pintype "passive"))
      (node (ref "E5") (pin "4") (pinfunction "4_4") (pintype "passive"))
    )
    (net (code "74") (name "Net-(E14A-O)") (class "Default")
      (node (ref "E14") (pin "3") (pinfunction "O_3") (pintype "output"))
      (node (ref "E16") (pin "12") (pinfunction "D_12") (pintype "input"))
    )
    (net (code "75") (name "Net-(E14D-O)") (class "Default")
      (node (ref "E14") (pin "11") (pinfunction "O_11") (pintype "output"))
      (node (ref "E8") (pin "10") (pinfunction "I1_10") (pintype "input"))
      (node (ref "E8") (pin "13") (pinfunction "I1_13") (pintype "input"))
      (node (ref "E8") (pin "5") (pinfunction "I1_5") (pintype "input"))
    )
    (net (code "76") (name "Net-(E16A-CLK)") (class "Default")
      (node (ref "E15") (pin "6") (pinfunction "6_6") (pintype "passive"))
      (node (ref "E16") (pin "3") (pinfunction "CLK_3") (pintype "input"))
    )
    (net (code "77") (name "Net-(E16A-D)") (class "Default")
      (node (ref "E1") (pin "10") (pinfunction "PRE_10") (pintype "input"))
      (node (ref "E1") (pin "4") (pinfunction "PRE_4") (pintype "input"))
      (node (ref "E16") (pin "13") (pinfunction "CLR_13") (pintype "input"))
      (node (ref "E16") (pin "2") (pinfunction "D_2") (pintype "input"))
      (node (ref "E16") (pin "4") (pinfunction "PRE_4") (pintype "input"))
      (node (ref "E2") (pin "10") (pinfunction "PRE_10") (pintype "input"))
      (node (ref "E2") (pin "4") (pinfunction "PRE_4") (pintype "input"))
      (node (ref "E4") (pin "10") (pinfunction "PRE_10") (pintype "input"))
      (node (ref "E4") (pin "4") (pinfunction "PRE_4") (pintype "input"))
      (node (ref "E7") (pin "10") (pinfunction "PRE_10") (pintype "input"))
      (node (ref "E7") (pin "4") (pinfunction "PRE_4") (pintype "input"))
      (node (ref "E9") (pin "10") (pinfunction "PRE_10") (pintype "input"))
      (node (ref "E9") (pin "12") (pinfunction "D_12") (pintype "input"))
      (node (ref "R5") (pin "1") (pinfunction "1_1") (pintype "passive"))
    )
    (net (code "78") (name "Net-(E16B-~{Q})") (class "Default")
      (node (ref "E10") (pin "3") (pinfunction "3_3") (pintype "passive"))
      (node (ref "E10") (pin "4") (pinfunction "4_4") (pintype "passive"))
      (node (ref "E16") (pin "8") (pinfunction "~{Q}_8") (pintype "output"))
    )
    (net (code "79") (name "Net-(Q1-B)") (class "Default")
      (node (ref "C26") (pin "1") (pinfunction "1_1") (pintype "passive"))
      (node (ref "Q1") (pin "2") (pinfunction "B_2") (pintype "passive"))
      (node (ref "R4") (pin "2") (pinfunction "2_2") (pintype "passive"))
    )
    (net (code "80") (name "Net-(Q1-C)") (class "Default")
      (node (ref "Q1") (pin "1") (pinfunction "C_1") (pintype "passive"))
      (node (ref "Q2") (pin "2") (pinfunction "B_2") (pintype "passive"))
      (node (ref "R2") (pin "1") (pinfunction "1_1") (pintype "passive"))
      (node (ref "R6") (pin "2") (pinfunction "2_2") (pintype "passive"))
    )
    (net (code "81") (name "Net-(Q1-E)") (class "Default")
      (node (ref "Q1") (pin "3") (pinfunction "E_3") (pintype "passive"))
      (node (ref "Q2") (pin "3") (pinfunction "E_3") (pintype "passive"))
      (node (ref "R1") (pin "1") (pinfunction "1_1") (pintype "passive"))
    )
    (net (code "82") (name "Net-(U$2A-1)") (class "Default")
      (node (ref "U$2") (pin "AA1") (pinfunction "1_AA1") (pintype "bidirectional"))
      (node (ref "U$7") (pin "A1") (pinfunction "P$1_A1") (pintype "passive"))
    )
    (net (code "83") (name "Net-(U$2AI-1)") (class "Default")
      (node (ref "U$2") (pin "AV1") (pinfunction "1_AV1") (pintype "bidirectional"))
      (node (ref "U$7") (pin "V1") (pinfunction "P$1_V1") (pintype "passive"))
    )
    (net (code "84") (name "Net-(U$2AK-1)") (class "Default")
      (node (ref "U$2") (pin "BA1") (pinfunction "1_BA1") (pintype "bidirectional"))
      (node (ref "U$5") (pin "A1") (pinfunction "P$1_A1") (pintype "passive"))
    )
    (net (code "85") (name "Net-(U$2AM-1)") (class "Default")
      (node (ref "U$2") (pin "BB1") (pinfunction "1_BB1") (pintype "bidirectional"))
      (node (ref "U$5") (pin "B1") (pinfunction "P$1_B1") (pintype "passive"))
    )
    (net (code "86") (name "Net-(U$2AN-1)") (class "Default")
      (node (ref "U$2") (pin "BB2") (pinfunction "1_BB2") (pintype "bidirectional"))
      (node (ref "U$5") (pin "B2") (pinfunction "P$1_B2") (pintype "passive"))
    )
    (net (code "87") (name "Net-(U$2AO-1)") (class "Default")
      (node (ref "U$2") (pin "BC1") (pinfunction "1_BC1") (pintype "bidirectional"))
      (node (ref "U$5") (pin "C1") (pinfunction "P$1_C1") (pintype "passive"))
    )
    (net (code "88") (name "Net-(U$2AW-1)") (class "Default")
      (node (ref "U$2") (pin "BH1") (pinfunction "1_BH1") (pintype "bidirectional"))
      (node (ref "U$5") (pin "H1") (pinfunction "P$1_H1") (pintype "passive"))
    )
    (net (code "89") (name "Net-(U$2AY-1)") (class "Default")
      (node (ref "U$2") (pin "BJ1") (pinfunction "1_BJ1") (pintype "bidirectional"))
      (node (ref "U$5") (pin "J1") (pinfunction "P$1_J1") (pintype "passive"))
    )
    (net (code "90") (name "Net-(U$2BB-1)") (class "Default")
      (node (ref "U$2") (pin "BK2") (pinfunction "1_BK2") (pintype "bidirectional"))
      (node (ref "U$5") (pin "K2") (pinfunction "P$1_K2") (pintype "passive"))
    )
    (net (code "91") (name "Net-(U$2BD-1)") (class "Default")
      (node (ref "U$2") (pin "BL2") (pinfunction "1_BL2") (pintype "bidirectional"))
      (node (ref "U$5") (pin "L2") (pinfunction "P$1_L2") (pintype "passive"))
    )
    (net (code "92") (name "Net-(U$2BF-1)") (class "Default")
      (node (ref "U$2") (pin "BM2") (pinfunction "1_BM2") (pintype "bidirectional"))
      (node (ref "U$5") (pin "M2") (pinfunction "P$1_M2") (pintype "passive"))
    )
    (net (code "93") (name "Net-(U$2BG-1)") (class "Default")
      (node (ref "U$2") (pin "BN1") (pinfunction "1_BN1") (pintype "bidirectional"))
      (node (ref "U$5") (pin "N1") (pinfunction "P$1_N1") (pintype "passive"))
    )
    (net (code "94") (name "Net-(U$2BI-1)") (class "Default")
      (node (ref "U$2") (pin "BP1") (pinfunction "1_BP1") (pintype "bidirectional"))
      (node (ref "U$5") (pin "P1") (pinfunction "P$1_P1") (pintype "passive"))
    )
    (net (code "95") (name "Net-(U$2BJ-1)") (class "Default")
      (node (ref "U$2") (pin "BP2") (pinfunction "1_BP2") (pintype "bidirectional"))
      (node (ref "U$5") (pin "P2") (pinfunction "P$1_P2") (pintype "passive"))
    )
    (net (code "96") (name "Net-(U$2BK-1)") (class "Default")
      (node (ref "U$2") (pin "BR1") (pinfunction "1_BR1") (pintype "bidirectional"))
      (node (ref "U$5") (pin "R1") (pinfunction "P$1_R1") (pintype "passive"))
    )
    (net (code "97") (name "Net-(U$2BL-1)") (class "Default")
      (node (ref "U$2") (pin "BR2") (pinfunction "1_BR2") (pintype "bidirectional"))
      (node (ref "U$5") (pin "R2") (pinfunction "P$1_R2") (pintype "passive"))
    )
    (net (code "98") (name "Net-(U$2BM-1)") (class "Default")
      (node (ref "U$2") (pin "BS1") (pinfunction "1_BS1") (pintype "bidirectional"))
      (node (ref "U$5") (pin "S1") (pinfunction "P$1_S1") (pintype "passive"))
    )
    (net (code "99") (name "Net-(U$2BP-1)") (class "Default")
      (node (ref "U$2") (pin "BT2") (pinfunction "1_BT2") (pintype "bidirectional"))
      (node (ref "U$5") (pin "T2") (pinfunction "P$1_T2") (pintype "passive"))
    )
    (net (code "100") (name "Net-(U$2BT-1)") (class "Default")
      (node (ref "U$2") (pin "BV2") (pinfunction "1_BV2") (pintype "bidirectional"))
      (node (ref "U$5") (pin "V2") (pinfunction "P$1_V2") (pintype "passive"))
    )
    (net (code "101") (name "Net-(U$2C-1)") (class "Default")
      (node (ref "U$2") (pin "AB1") (pinfunction "1_AB1") (pintype "bidirectional"))
      (node (ref "U$7") (pin "B1") (pinfunction "P$1_B1") (pintype "passive"))
    )
    (net (code "102") (name "Net-(U$2D-1)") (class "Default")
      (node (ref "U$2") (pin "AB2") (pinfunction "1_AB2") (pintype "bidirectional"))
      (node (ref "U$7") (pin "B2") (pinfunction "P$1_B2") (pintype "passive"))
    )
    (net (code "103") (name "Net-(U$2E-1)") (class "Default")
      (node (ref "U$2") (pin "AC1") (pinfunction "1_AC1") (pintype "bidirectional"))
      (node (ref "U$7") (pin "C1") (pinfunction "P$1_C1") (pintype "passive"))
    )
    (net (code "104") (name "VCC") (class "Default")
      (node (ref "C1") (pin "1") (pinfunction "1_1") (pintype "passive"))
      (node (ref "C10") (pin "1") (pinfunction "1_1") (pintype "passive"))
      (node (ref "C11") (pin "1") (pinfunction "1_1") (pintype "passive"))
      (node (ref "C12") (pin "1") (pinfunction "1_1") (pintype "passive"))
      (node (ref "C13") (pin "1") (pinfunction "1_1") (pintype "passive"))
      (node (ref "C14") (pin "1") (pinfunction "1_1") (pintype "passive"))
      (node (ref "C15") (pin "1") (pinfunction "1_1") (pintype "passive"))
      (node (ref "C16") (pin "1") (pinfunction "1_1") (pintype "passive"))
      (node (ref "C17") (pin "1") (pinfunction "1_1") (pintype "passive"))
      (node (ref "C18") (pin "1") (pinfunction "1_1") (pintype "passive"))
      (node (ref "C19") (pin "1") (pinfunction "1_1") (pintype "passive"))
      (node (ref "C2") (pin "1") (pinfunction "1_1") (pintype "passive"))
      (node (ref "C20") (pin "1") (pinfunction "1_1") (pintype "passive"))
      (node (ref "C21") (pin "1") (pinfunction "1_1") (pintype "passive"))
      (node (ref "C3") (pin "1") (pinfunction "1_1") (pintype "passive"))
      (node (ref "C4") (pin "1") (pinfunction "1_1") (pintype "passive"))
      (node (ref "C5") (pin "1") (pinfunction "1_1") (pintype "passive"))
      (node (ref "C6") (pin "1") (pinfunction "1_1") (pintype "passive"))
      (node (ref "C7") (pin "1") (pinfunction "1_1") (pintype "passive"))
      (node (ref "C8") (pin "1") (pinfunction "1_1") (pintype "passive"))
      (node (ref "C9") (pin "1") (pinfunction "1_1") (pintype "passive"))
      (node (ref "E10") (pin "14") (pinfunction "14_14") (pintype "passive"))
      (node (ref "E15") (pin "14") (pinfunction "14_14") (pintype "passive"))
      (node (ref "E5") (pin "14") (pinfunction "14_14") (pintype "passive"))
      (node (ref "R1") (pin "2") (pinfunction "2_2") (pintype "passive"))
      (node (ref "R10") (pin "2") (pinfunction "2_2") (pintype "passive"))
      (node (ref "R11") (pin "2") (pinfunction "2_2") (pintype "passive"))
      (node (ref "R13") (pin "2") (pinfunction "2_2") (pintype "passive"))
      (node (ref "R14") (pin "2") (pinfunction "2_2") (pintype "passive"))
      (node (ref "R2") (pin "2") (pinfunction "2_2") (pintype "passive"))
      (node (ref "R3") (pin "2") (pinfunction "2_2") (pintype "passive"))
      (node (ref "R5") (pin "2") (pinfunction "2_2") (pintype "passive"))
      (node (ref "R8") (pin "2") (pinfunction "2_2") (pintype "passive"))
      (node (ref "R9") (pin "2") (pinfunction "2_2") (pintype "passive"))
      (node (ref "U$2") (pin "AA2") (pinfunction "1_AA2") (pintype "bidirectional"))
      (node (ref "U$2") (pin "BA2") (pinfunction "1_BA2") (pintype "bidirectional"))
      (node (ref "U$5") (pin "A2") (pinfunction "P$1_A2") (pintype "passive"))
      (node (ref "U$7") (pin "A2") (pinfunction "P$1_A2") (pintype "passive"))
    )
    (net (code "105") (name "unconnected-(E1A-Q-Pad5)") (class "Default")
      (node (ref "E1") (pin "5") (pinfunction "Q_5") (pintype "output"))
    )
    (net (code "106") (name "unconnected-(E1B-Q-Pad9)") (class "Default")
      (node (ref "E1") (pin "9") (pinfunction "Q_9") (pintype "output"))
    )
    (net (code "107") (name "unconnected-(E2A-Q-Pad5)") (class "Default")
      (node (ref "E2") (pin "5") (pinfunction "Q_5") (pintype "output"))
    )
    (net (code "108") (name "unconnected-(E2B-Q-Pad9)") (class "Default")
      (node (ref "E2") (pin "9") (pinfunction "Q_9") (pintype "output"))
    )
    (net (code "109") (name "unconnected-(E4A-Q-Pad5)") (class "Default")
      (node (ref "E4") (pin "5") (pinfunction "Q_5") (pintype "output"))
    )
    (net (code "110") (name "unconnected-(E4B-Q-Pad9)") (class "Default")
      (node (ref "E4") (pin "9") (pinfunction "Q_9") (pintype "output"))
    )
    (net (code "111") (name "unconnected-(E5-Pad5)") (class "Default")
      (node (ref "E5") (pin "5") (pinfunction "5_5") (pintype "passive"))
    )
    (net (code "112") (name "unconnected-(E5-Pad6)") (class "Default")
      (node (ref "E5") (pin "6") (pinfunction "6_6") (pintype "passive"))
    )
    (net (code "113") (name "unconnected-(E5-Pad9)") (class "Default")
      (node (ref "E5") (pin "9") (pinfunction "9_9") (pintype "passive"))
    )
    (net (code "114") (name "unconnected-(E5-Pad10)") (class "Default")
      (node (ref "E5") (pin "10") (pinfunction "10_10") (pintype "passive"))
    )
    (net (code "115") (name "unconnected-(E5-Pad12)") (class "Default")
      (node (ref "E5") (pin "12") (pinfunction "12_12") (pintype "passive"))
    )
    (net (code "116") (name "unconnected-(E7A-Q-Pad5)") (class "Default")
      (node (ref "E7") (pin "5") (pinfunction "Q_5") (pintype "output"))
    )
    (net (code "117") (name "unconnected-(E7B-Q-Pad9)") (class "Default")
      (node (ref "E7") (pin "9") (pinfunction "Q_9") (pintype "output"))
    )
    (net (code "118") (name "unconnected-(E9A-Q-Pad5)") (class "Default")
      (node (ref "E9") (pin "5") (pinfunction "Q_5") (pintype "output"))
    )
    (net (code "119") (name "unconnected-(E9B-~{Q}-Pad8)") (class "Default")
      (node (ref "E9") (pin "8") (pinfunction "~{Q}_8") (pintype "output"))
    )
    (net (code "120") (name "unconnected-(E10-Pad5)") (class "Default")
      (node (ref "E10") (pin "5") (pinfunction "5_5") (pintype "passive"))
    )
    (net (code "121") (name "unconnected-(E10-Pad8)") (class "Default")
      (node (ref "E10") (pin "8") (pinfunction "8_8") (pintype "passive"))
    )
    (net (code "122") (name "unconnected-(E10-Pad9)") (class "Default")
      (node (ref "E10") (pin "9") (pinfunction "9_9") (pintype "passive"))
    )
    (net (code "123") (name "unconnected-(E10-Pad10)") (class "Default")
      (node (ref "E10") (pin "10") (pinfunction "10_10") (pintype "passive"))
    )
    (net (code "124") (name "unconnected-(E10-Pad12)") (class "Default")
      (node (ref "E10") (pin "12") (pinfunction "12_12") (pintype "passive"))
    )
    (net (code "125") (name "unconnected-(E15-Pad5)") (class "Default")
      (node (ref "E15") (pin "5") (pinfunction "5_5") (pintype "passive"))
    )
    (net (code "126") (name "unconnected-(E15-Pad8)") (class "Default")
      (node (ref "E15") (pin "8") (pinfunction "8_8") (pintype "passive"))
    )
    (net (code "127") (name "unconnected-(E15-Pad9)") (class "Default")
      (node (ref "E15") (pin "9") (pinfunction "9_9") (pintype "passive"))
    )
    (net (code "128") (name "unconnected-(E15-Pad10)") (class "Default")
      (node (ref "E15") (pin "10") (pinfunction "10_10") (pintype "passive"))
    )
    (net (code "129") (name "unconnected-(E15-Pad12)") (class "Default")
      (node (ref "E15") (pin "12") (pinfunction "12_12") (pintype "passive"))
    )
    (net (code "130") (name "unconnected-(E16A-~{Q}-Pad6)") (class "Default")
      (node (ref "E16") (pin "6") (pinfunction "~{Q}_6") (pintype "output"))
    )
  )
)
